# CEM-3310-VCADSR-MB.net
KiCad netlist of a schematic drawn in EAGLE
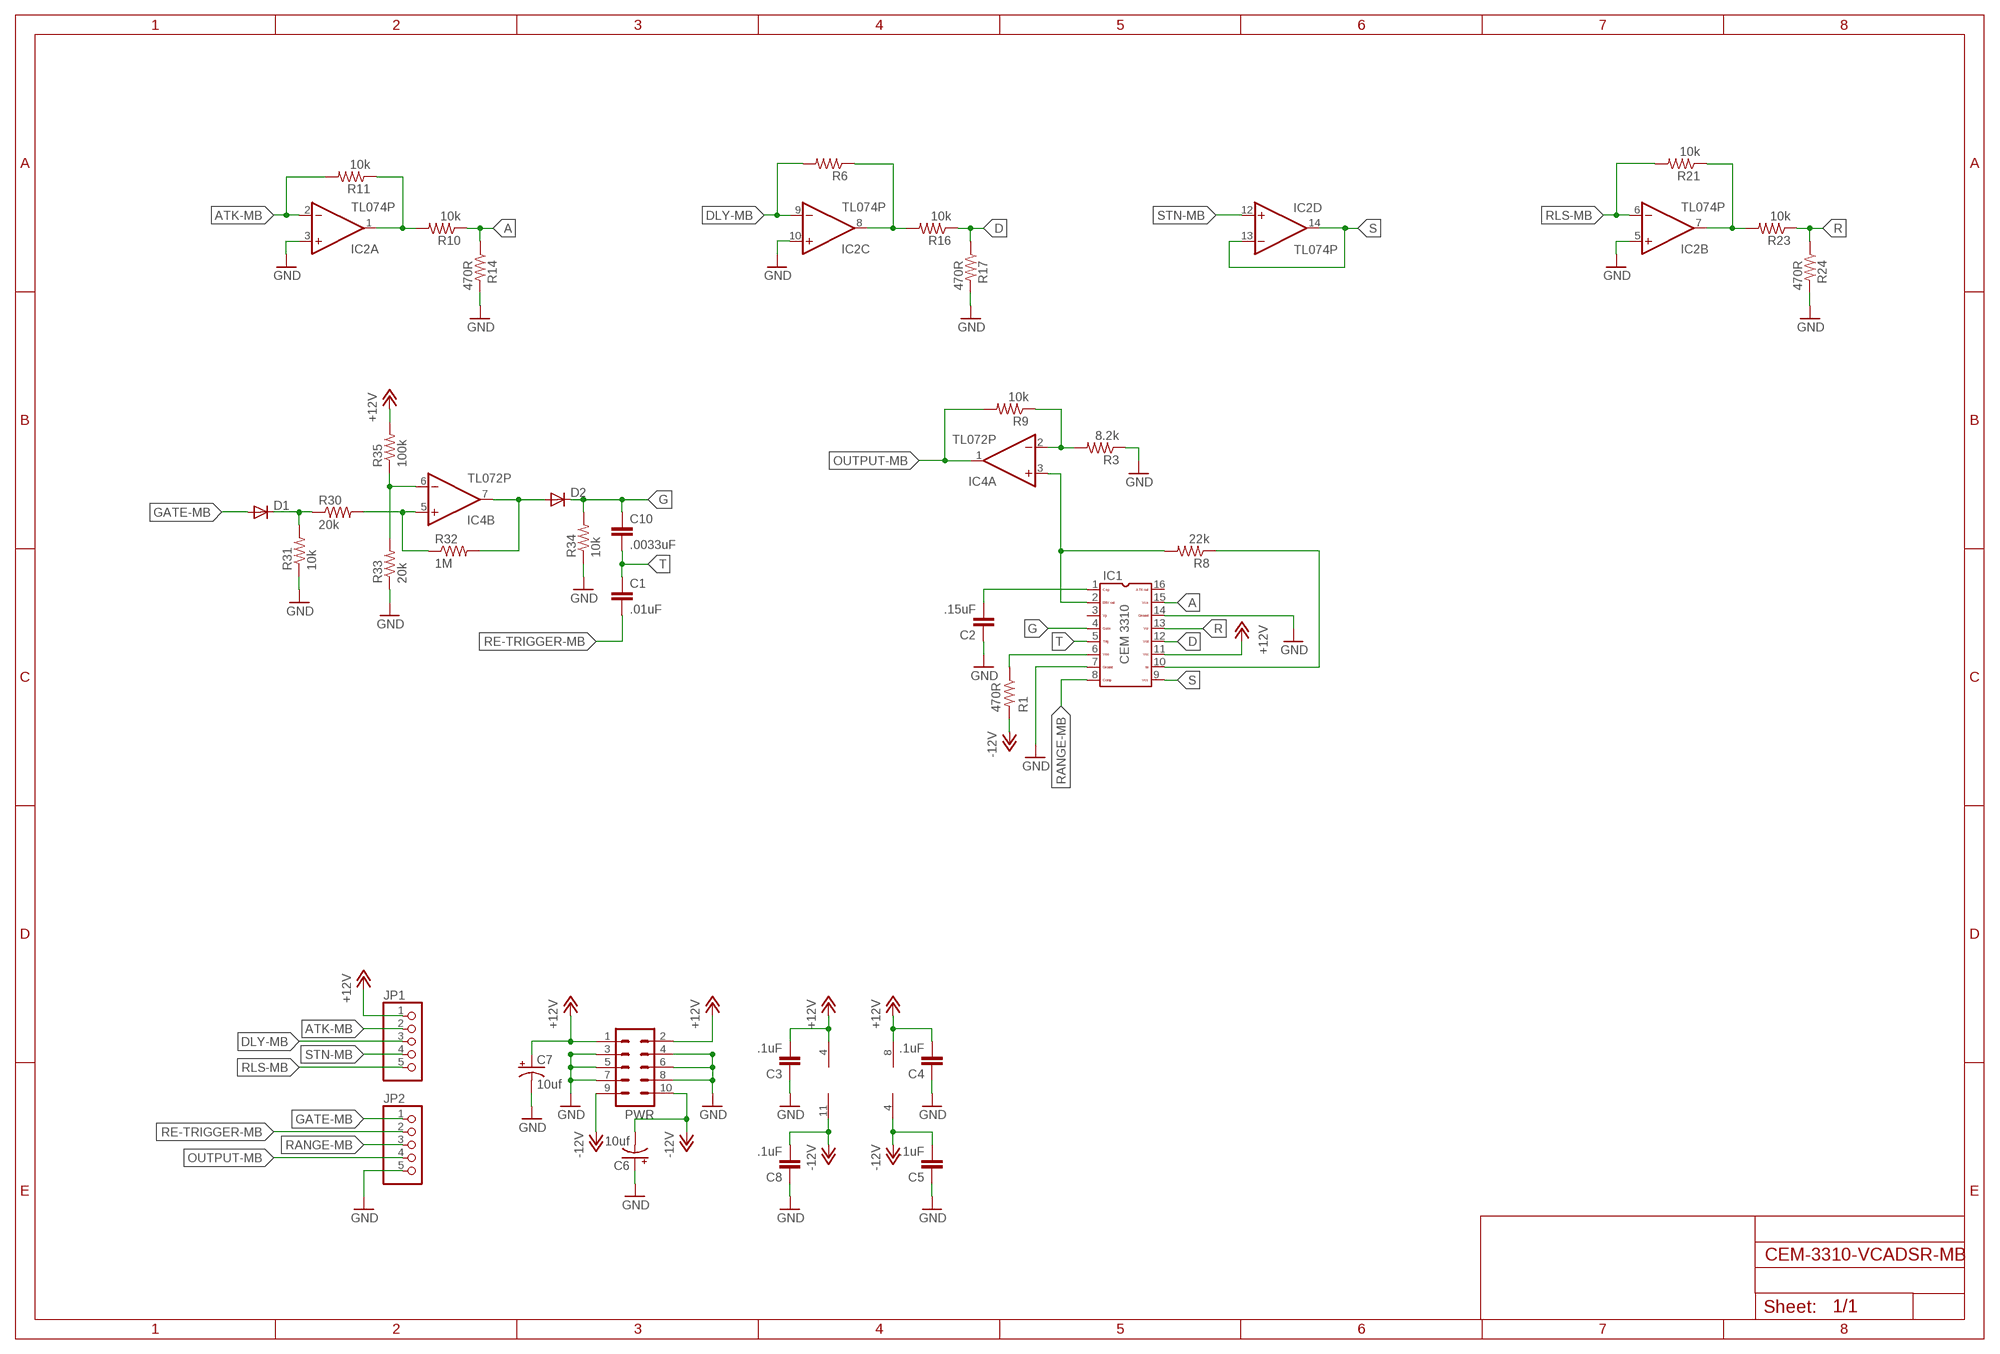
[diagram p0: schematic, sheet 1]

(export (version "E")
  (design (tool "Eeschema 10.0.6"))
  (components
    (comp (ref "C1")
      (value ".01uF")
      (footprint "eagle-import:C050-024X044")
      (libsource (lib "eagle-import") (part "C-EU050-024X044"))
    )
    (comp (ref "C2")
      (value ".15uF")
      (footprint "eagle-import:C050-024X044")
      (libsource (lib "eagle-import") (part "C-EU050-024X044"))
    )
    (comp (ref "C3")
      (value ".1uF")
      (footprint "eagle-import:C050-024X044")
      (libsource (lib "eagle-import") (part "C-EU050-024X044"))
    )
    (comp (ref "C4")
      (value ".1uF")
      (footprint "eagle-import:C050-024X044")
      (libsource (lib "eagle-import") (part "C-EU050-024X044"))
    )
    (comp (ref "C5")
      (value ".1uF")
      (footprint "eagle-import:C050-024X044")
      (libsource (lib "eagle-import") (part "C-EU050-024X044"))
    )
    (comp (ref "C6")
      (value "10uf")
      (footprint "eagle-import:E2,5-5")
      (libsource (lib "eagle-import") (part "CPOL-USE2.5-5"))
    )
    (comp (ref "C7")
      (value "10uf")
      (footprint "eagle-import:E2,5-5")
      (libsource (lib "eagle-import") (part "CPOL-USE2.5-5"))
    )
    (comp (ref "C8")
      (value ".1uF")
      (footprint "eagle-import:C050-024X044")
      (libsource (lib "eagle-import") (part "C-EU050-024X044"))
    )
    (comp (ref "C10")
      (value ".0033uF")
      (footprint "eagle-import:C050-024X044")
      (libsource (lib "eagle-import") (part "C-EU050-024X044"))
    )
    (comp (ref "D1")
      (value "1N4148DO35-7")
      (footprint "eagle-import:DO35-7")
      (libsource (lib "eagle-import") (part "1N4148DO35-7"))
    )
    (comp (ref "D2")
      (value "1N4148DO35-7")
      (footprint "eagle-import:DO35-7")
      (libsource (lib "eagle-import") (part "1N4148DO35-7"))
    )
    (comp (ref "IC1")
      (value "CEM3310")
      (footprint "eagle-import:DIL16")
      (libsource (lib "eagle-import") (part "CEM3310"))
    )
    (comp (ref "IC2")
      (value "TL074P")
      (footprint "eagle-import:DIL14")
      (libsource (lib "eagle-import") (part "TL074P"))
    )
    (comp (ref "IC4")
      (value "TL072P")
      (footprint "eagle-import:DIL08")
      (libsource (lib "eagle-import") (part "TL072P"))
    )
    (comp (ref "JP1")
      (value "PINHD-1X5")
      (footprint "eagle-import:1X05")
      (libsource (lib "eagle-import") (part "PINHD-1X5"))
    )
    (comp (ref "JP2")
      (value "PINHD-1X5")
      (footprint "eagle-import:1X05")
      (libsource (lib "eagle-import") (part "PINHD-1X5"))
    )
    (comp (ref "PWR")
      (value "ML10")
      (footprint "eagle-import:ML10")
      (libsource (lib "eagle-import") (part "ML10"))
    )
    (comp (ref "R1")
      (value "470R")
      (footprint "eagle-import:0207_7")
      (libsource (lib "eagle-import") (part "R-US_0207/7"))
    )
    (comp (ref "R3")
      (value "8.2k")
      (footprint "eagle-import:0207_7")
      (libsource (lib "eagle-import") (part "R-US_0207/7"))
    )
    (comp (ref "R6")
      (value "10k")
      (footprint "eagle-import:0207_7")
      (libsource (lib "eagle-import") (part "R-US_0207/7"))
    )
    (comp (ref "R8")
      (value "22k")
      (footprint "eagle-import:0207_7")
      (libsource (lib "eagle-import") (part "R-US_0207/7"))
    )
    (comp (ref "R9")
      (value "10k")
      (footprint "eagle-import:0207_7")
      (libsource (lib "eagle-import") (part "R-US_0207/7"))
    )
    (comp (ref "R10")
      (value "10k")
      (footprint "eagle-import:0207_7")
      (libsource (lib "eagle-import") (part "R-US_0207/7"))
    )
    (comp (ref "R11")
      (value "10k")
      (footprint "eagle-import:0207_7")
      (libsource (lib "eagle-import") (part "R-US_0207/7"))
    )
    (comp (ref "R14")
      (value "470R")
      (footprint "eagle-import:0207_7")
      (libsource (lib "eagle-import") (part "R-US_0207/7"))
    )
    (comp (ref "R16")
      (value "10k")
      (footprint "eagle-import:0207_7")
      (libsource (lib "eagle-import") (part "R-US_0207/7"))
    )
    (comp (ref "R17")
      (value "470R")
      (footprint "eagle-import:0207_7")
      (libsource (lib "eagle-import") (part "R-US_0207/7"))
    )
    (comp (ref "R21")
      (value "10k")
      (footprint "eagle-import:0207_7")
      (libsource (lib "eagle-import") (part "R-US_0207/7"))
    )
    (comp (ref "R23")
      (value "10k")
      (footprint "eagle-import:0207_7")
      (libsource (lib "eagle-import") (part "R-US_0207/7"))
    )
    (comp (ref "R24")
      (value "470R")
      (footprint "eagle-import:0207_7")
      (libsource (lib "eagle-import") (part "R-US_0207/7"))
    )
    (comp (ref "R30")
      (value "20k")
      (footprint "eagle-import:0207_7")
      (libsource (lib "eagle-import") (part "R-US_0207/7"))
    )
    (comp (ref "R31")
      (value "10k")
      (footprint "eagle-import:0207_7")
      (libsource (lib "eagle-import") (part "R-US_0207/7"))
    )
    (comp (ref "R32")
      (value "1M")
      (footprint "eagle-import:0207_7")
      (libsource (lib "eagle-import") (part "R-US_0207/7"))
    )
    (comp (ref "R33")
      (value "20k")
      (footprint "eagle-import:0207_7")
      (libsource (lib "eagle-import") (part "R-US_0207/7"))
    )
    (comp (ref "R34")
      (value "10k")
      (footprint "eagle-import:0207_7")
      (libsource (lib "eagle-import") (part "R-US_0207/7"))
    )
    (comp (ref "R35")
      (value "100k")
      (footprint "eagle-import:0207_7")
      (libsource (lib "eagle-import") (part "R-US_0207/7"))
    )
  )
  (nets
    (net (code "1") (name "+12V") (class "Default")
      (node (ref "C3") (pin "2") (pinfunction "2_2") (pintype "passive"))
      (node (ref "C4") (pin "2") (pinfunction "2_2") (pintype "passive"))
      (node (ref "C7") (pin "+") (pinfunction "+_+") (pintype "passive"))
      (node (ref "IC1") (pin "11") (pinfunction "11_11") (pintype "power_in"))
      (node (ref "IC2") (pin "4") (pinfunction "V+_4") (pintype "power_in"))
      (node (ref "IC4") (pin "8") (pinfunction "V+_8") (pintype "power_in"))
      (node (ref "JP1") (pin "1") (pinfunction "1_1") (pintype "passive"))
      (node (ref "PWR") (pin "1") (pinfunction "1_1") (pintype "passive"))
      (node (ref "PWR") (pin "2") (pinfunction "2_2") (pintype "passive"))
      (node (ref "R35") (pin "2") (pinfunction "2_2") (pintype "passive"))
    )
    (net (code "2") (name "-12V") (class "Default")
      (node (ref "C5") (pin "2") (pinfunction "2_2") (pintype "passive"))
      (node (ref "C6") (pin "-") (pinfunction "-_-") (pintype "passive"))
      (node (ref "C8") (pin "2") (pinfunction "2_2") (pintype "passive"))
      (node (ref "IC2") (pin "11") (pinfunction "V-_11") (pintype "power_in"))
      (node (ref "IC4") (pin "4") (pinfunction "V-_4") (pintype "power_in"))
      (node (ref "PWR") (pin "10") (pinfunction "10_10") (pintype "passive"))
      (node (ref "PWR") (pin "9") (pinfunction "9_9") (pintype "passive"))
      (node (ref "R1") (pin "2") (pinfunction "2_2") (pintype "passive"))
    )
    (net (code "3") (name "A") (class "Default")
      (node (ref "IC1") (pin "15") (pinfunction "15_15") (pintype "power_in"))
      (node (ref "R10") (pin "1") (pinfunction "1_1") (pintype "passive"))
      (node (ref "R14") (pin "1") (pinfunction "1_1") (pintype "passive"))
    )
    (net (code "4") (name "ATK-MB") (class "Default")
      (node (ref "IC2") (pin "2") (pinfunction "-IN_2") (pintype "input"))
      (node (ref "JP1") (pin "2") (pinfunction "2_2") (pintype "passive"))
      (node (ref "R11") (pin "2") (pinfunction "2_2") (pintype "passive"))
    )
    (net (code "5") (name "D") (class "Default")
      (node (ref "IC1") (pin "12") (pinfunction "12_12") (pintype "power_in"))
      (node (ref "R16") (pin "1") (pinfunction "1_1") (pintype "passive"))
      (node (ref "R17") (pin "1") (pinfunction "1_1") (pintype "passive"))
    )
    (net (code "6") (name "DLY-MB") (class "Default")
      (node (ref "IC2") (pin "9") (pinfunction "-IN_9") (pintype "input"))
      (node (ref "JP1") (pin "3") (pinfunction "3_3") (pintype "passive"))
      (node (ref "R6") (pin "2") (pinfunction "2_2") (pintype "passive"))
    )
    (net (code "7") (name "G") (class "Default")
      (node (ref "C10") (pin "1") (pinfunction "1_1") (pintype "passive"))
      (node (ref "D2") (pin "C") (pinfunction "C_C") (pintype "passive"))
      (node (ref "IC1") (pin "4") (pinfunction "4_4") (pintype "input"))
      (node (ref "R34") (pin "2") (pinfunction "2_2") (pintype "passive"))
    )
    (net (code "8") (name "GATE-MB") (class "Default")
      (node (ref "D1") (pin "A") (pinfunction "A_A") (pintype "passive"))
      (node (ref "JP2") (pin "1") (pinfunction "1_1") (pintype "passive"))
    )
    (net (code "9") (name "GND") (class "Default")
      (node (ref "C2") (pin "1") (pinfunction "1_1") (pintype "passive"))
      (node (ref "C3") (pin "1") (pinfunction "1_1") (pintype "passive"))
      (node (ref "C4") (pin "1") (pinfunction "1_1") (pintype "passive"))
      (node (ref "C5") (pin "1") (pinfunction "1_1") (pintype "passive"))
      (node (ref "C6") (pin "+") (pinfunction "+_+") (pintype "passive"))
      (node (ref "C7") (pin "-") (pinfunction "-_-") (pintype "passive"))
      (node (ref "C8") (pin "1") (pinfunction "1_1") (pintype "passive"))
      (node (ref "IC1") (pin "14") (pinfunction "14_14") (pintype "power_in"))
      (node (ref "IC1") (pin "7") (pinfunction "7_7") (pintype "power_in"))
      (node (ref "IC2") (pin "10") (pinfunction "+IN_10") (pintype "input"))
      (node (ref "IC2") (pin "3") (pinfunction "+IN_3") (pintype "input"))
      (node (ref "IC2") (pin "5") (pinfunction "+IN_5") (pintype "input"))
      (node (ref "JP2") (pin "5") (pinfunction "5_5") (pintype "passive"))
      (node (ref "PWR") (pin "3") (pinfunction "3_3") (pintype "passive"))
      (node (ref "PWR") (pin "4") (pinfunction "4_4") (pintype "passive"))
      (node (ref "PWR") (pin "5") (pinfunction "5_5") (pintype "passive"))
      (node (ref "PWR") (pin "6") (pinfunction "6_6") (pintype "passive"))
      (node (ref "PWR") (pin "7") (pinfunction "7_7") (pintype "passive"))
      (node (ref "PWR") (pin "8") (pinfunction "8_8") (pintype "passive"))
      (node (ref "R14") (pin "2") (pinfunction "2_2") (pintype "passive"))
      (node (ref "R17") (pin "2") (pinfunction "2_2") (pintype "passive"))
      (node (ref "R24") (pin "2") (pinfunction "2_2") (pintype "passive"))
      (node (ref "R3") (pin "1") (pinfunction "1_1") (pintype "passive"))
      (node (ref "R31") (pin "1") (pinfunction "1_1") (pintype "passive"))
      (node (ref "R33") (pin "1") (pinfunction "1_1") (pintype "passive"))
      (node (ref "R34") (pin "1") (pinfunction "1_1") (pintype "passive"))
    )
    (net (code "10") (name "Net-(C2-Pad2)") (class "Default")
      (node (ref "C2") (pin "2") (pinfunction "2_2") (pintype "passive"))
      (node (ref "IC1") (pin "1") (pinfunction "1_1") (pintype "bidirectional"))
    )
    (net (code "11") (name "Net-(D1-PadC)") (class "Default")
      (node (ref "D1") (pin "C") (pinfunction "C_C") (pintype "passive"))
      (node (ref "R30") (pin "1") (pinfunction "1_1") (pintype "passive"))
      (node (ref "R31") (pin "2") (pinfunction "2_2") (pintype "passive"))
    )
    (net (code "12") (name "Net-(IC1-Pad6)") (class "Default")
      (node (ref "IC1") (pin "6") (pinfunction "6_6") (pintype "power_in"))
      (node (ref "R1") (pin "1") (pinfunction "1_1") (pintype "passive"))
    )
    (net (code "13") (name "Net-(IC1-Pad10)") (class "Default")
      (node (ref "IC1") (pin "10") (pinfunction "10_10") (pintype "power_in"))
      (node (ref "R8") (pin "1") (pinfunction "1_1") (pintype "passive"))
    )
    (net (code "14") (name "Net-(IC2A-OUT)") (class "Default")
      (node (ref "IC2") (pin "1") (pinfunction "OUT_1") (pintype "output"))
      (node (ref "R10") (pin "2") (pinfunction "2_2") (pintype "passive"))
      (node (ref "R11") (pin "1") (pinfunction "1_1") (pintype "passive"))
    )
    (net (code "15") (name "Net-(IC2B-OUT)") (class "Default")
      (node (ref "IC2") (pin "7") (pinfunction "OUT_7") (pintype "output"))
      (node (ref "R21") (pin "1") (pinfunction "1_1") (pintype "passive"))
      (node (ref "R23") (pin "2") (pinfunction "2_2") (pintype "passive"))
    )
    (net (code "16") (name "Net-(IC2C-OUT)") (class "Default")
      (node (ref "IC2") (pin "8") (pinfunction "OUT_8") (pintype "output"))
      (node (ref "R16") (pin "2") (pinfunction "2_2") (pintype "passive"))
      (node (ref "R6") (pin "1") (pinfunction "1_1") (pintype "passive"))
    )
    (net (code "17") (name "Net-(IC4A-+IN)") (class "Default")
      (node (ref "IC1") (pin "2") (pinfunction "2_2") (pintype "output"))
      (node (ref "IC4") (pin "3") (pinfunction "+IN_3") (pintype "input"))
      (node (ref "R8") (pin "2") (pinfunction "2_2") (pintype "passive"))
    )
    (net (code "18") (name "Net-(IC4A--IN)") (class "Default")
      (node (ref "IC4") (pin "2") (pinfunction "-IN_2") (pintype "input"))
      (node (ref "R3") (pin "2") (pinfunction "2_2") (pintype "passive"))
      (node (ref "R9") (pin "1") (pinfunction "1_1") (pintype "passive"))
    )
    (net (code "19") (name "Net-(IC4B-+IN)") (class "Default")
      (node (ref "IC4") (pin "5") (pinfunction "+IN_5") (pintype "input"))
      (node (ref "R30") (pin "2") (pinfunction "2_2") (pintype "passive"))
      (node (ref "R32") (pin "1") (pinfunction "1_1") (pintype "passive"))
    )
    (net (code "20") (name "Net-(IC4B--IN)") (class "Default")
      (node (ref "IC4") (pin "6") (pinfunction "-IN_6") (pintype "input"))
      (node (ref "R33") (pin "2") (pinfunction "2_2") (pintype "passive"))
      (node (ref "R35") (pin "1") (pinfunction "1_1") (pintype "passive"))
    )
    (net (code "21") (name "Net-(IC4B-OUT)") (class "Default")
      (node (ref "D2") (pin "A") (pinfunction "A_A") (pintype "passive"))
      (node (ref "IC4") (pin "7") (pinfunction "OUT_7") (pintype "output"))
      (node (ref "R32") (pin "2") (pinfunction "2_2") (pintype "passive"))
    )
    (net (code "22") (name "OUTPUT-MB") (class "Default")
      (node (ref "IC4") (pin "1") (pinfunction "OUT_1") (pintype "output"))
      (node (ref "JP2") (pin "4") (pinfunction "4_4") (pintype "passive"))
      (node (ref "R9") (pin "2") (pinfunction "2_2") (pintype "passive"))
    )
    (net (code "23") (name "R") (class "Default")
      (node (ref "IC1") (pin "13") (pinfunction "13_13") (pintype "power_in"))
      (node (ref "R23") (pin "1") (pinfunction "1_1") (pintype "passive"))
      (node (ref "R24") (pin "1") (pinfunction "1_1") (pintype "passive"))
    )
    (net (code "24") (name "RANGE-MB") (class "Default")
      (node (ref "IC1") (pin "8") (pinfunction "8_8") (pintype "bidirectional"))
      (node (ref "JP2") (pin "3") (pinfunction "3_3") (pintype "passive"))
    )
    (net (code "25") (name "RE-TRIGGER-MB") (class "Default")
      (node (ref "C1") (pin "2") (pinfunction "2_2") (pintype "passive"))
      (node (ref "JP2") (pin "2") (pinfunction "2_2") (pintype "passive"))
    )
    (net (code "26") (name "RLS-MB") (class "Default")
      (node (ref "IC2") (pin "6") (pinfunction "-IN_6") (pintype "input"))
      (node (ref "JP1") (pin "5") (pinfunction "5_5") (pintype "passive"))
      (node (ref "R21") (pin "2") (pinfunction "2_2") (pintype "passive"))
    )
    (net (code "27") (name "S") (class "Default")
      (node (ref "IC1") (pin "9") (pinfunction "9_9") (pintype "power_in"))
      (node (ref "IC2") (pin "13") (pinfunction "-IN_13") (pintype "input"))
      (node (ref "IC2") (pin "14") (pinfunction "OUT_14") (pintype "output"))
    )
    (net (code "28") (name "STN-MB") (class "Default")
      (node (ref "IC2") (pin "12") (pinfunction "+IN_12") (pintype "input"))
      (node (ref "JP1") (pin "4") (pinfunction "4_4") (pintype "passive"))
    )
    (net (code "29") (name "T") (class "Default")
      (node (ref "C1") (pin "1") (pinfunction "1_1") (pintype "passive"))
      (node (ref "C10") (pin "2") (pinfunction "2_2") (pintype "passive"))
      (node (ref "IC1") (pin "5") (pinfunction "5_5") (pintype "input"))
    )
    (net (code "30") (name "unconnected-(IC1-Pad3)") (class "Default")
      (node (ref "IC1") (pin "3") (pinfunction "3_3") (pintype "bidirectional"))
    )
    (net (code "31") (name "unconnected-(IC1-Pad16)") (class "Default")
      (node (ref "IC1") (pin "16") (pinfunction "16_16") (pintype "output"))
    )
  )
)
